# nguon.net
KiCad netlist of a schematic drawn in Altium Designer
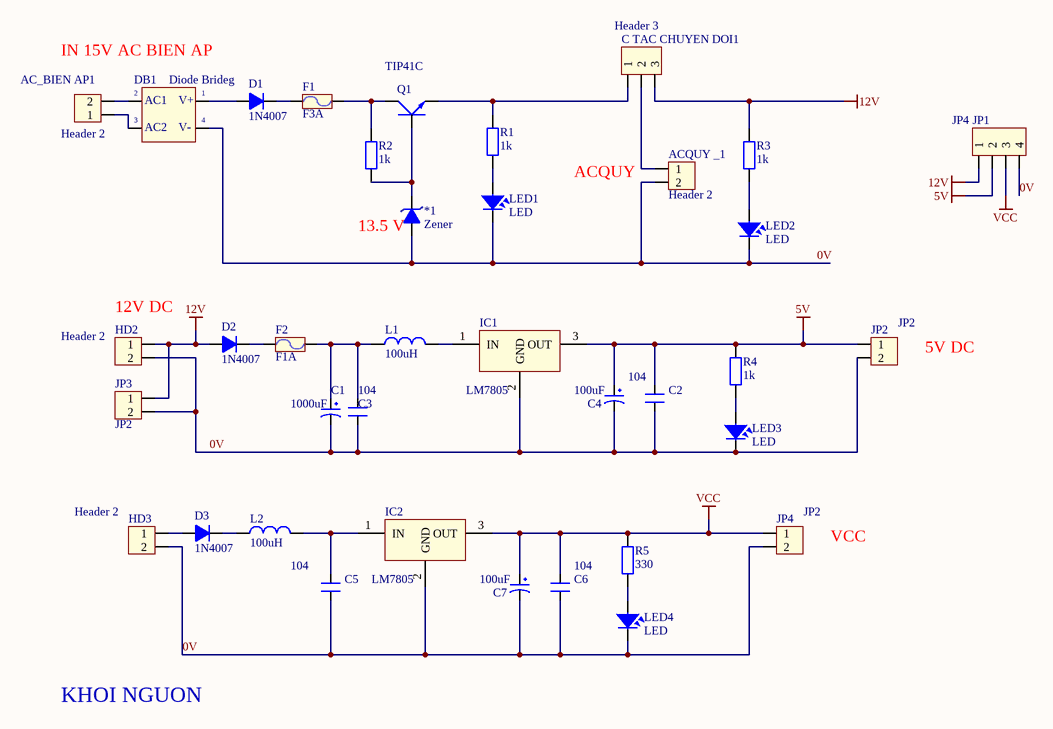
[diagram p0: nguon.SchDoc]

(export (version "E")
  (design (tool "Eeschema 10.0.6"))
  (components
    (comp (ref "*1") (value "Zener") (footprint "D1A") (libsource (lib "syhaunguyen") (part "Zener")))
    (comp (ref "ACQUY _1")
      (value "Header 2")
      (footprint "HED2")
      (description "Header 2 (Green)")
      (libsource (lib "") (part "Hed2_2"))
    )
    (comp (ref "AC_BIEN AP1")
      (value "Header 2")
      (footprint "HED2")
      (description "Header 2 (Green)")
      (libsource (lib "") (part "Hed2_1"))
    )
    (comp (ref "C TAC CHUYEN DOI1")
      (value "Header 3")
      (footprint "HED3")
      (description "Header 3 (Green)")
      (libsource (lib "syhaunguyen") (part "Hed3"))
    )
    (comp (ref "C1")
      (value "1000uF")
      (footprint "CP1.5/3.4")
      (description "Cap 1000uF/16V - 220uF/50V")
      (libsource (lib "syhaunguyen") (part "CP4"))
    )
    (comp (ref "C2")
      (value "104")
      (footprint "CN2")
      (description "Cap np Cremic Value  104pF => 105pF")
      (libsource (lib "syhaunguyen") (part "CN2"))
    )
    (comp (ref "C3")
      (value "104")
      (footprint "CN2")
      (description "Cap np Cremic Value  104pF => 105pF")
      (libsource (lib "syhaunguyen") (part "CN2"))
    )
    (comp (ref "C4")
      (value "100uF")
      (footprint "CP1/2.5")
      (description "C 47uF/50V , 220uF/16V")
      (libsource (lib "syhaunguyen") (part "CP2"))
    )
    (comp (ref "C5")
      (value "104")
      (footprint "CN2")
      (description "Cap np Cremic Value  104pF => 105pF")
      (libsource (lib "syhaunguyen") (part "CN2"))
    )
    (comp (ref "C6")
      (value "104")
      (footprint "CN2")
      (description "Cap np Cremic Value  104pF => 105pF")
      (libsource (lib "syhaunguyen") (part "CN2"))
    )
    (comp (ref "C7")
      (value "100uF")
      (footprint "CP1/2.5")
      (description "C 47uF/50V , 220uF/16V")
      (libsource (lib "syhaunguyen") (part "CP2"))
    )
    (comp (ref "D1")
      (value "1N4007")
      (footprint "D1A")
      (description "Diode 1A")
      (libsource (lib "syhaunguyen") (part "D1A"))
    )
    (comp (ref "D2")
      (value "1N4007")
      (footprint "D1A")
      (description "Diode 1A")
      (libsource (lib "syhaunguyen") (part "D1A"))
    )
    (comp (ref "D3")
      (value "1N4007")
      (footprint "D1A")
      (description "Diode 1A")
      (libsource (lib "syhaunguyen") (part "D1A"))
    )
    (comp (ref "DB1")
      (value "Diode Brideg")
      (footprint "CAU 1A")
      (description "Convert AC to DC voltage, 4 pin")
      (libsource (lib "syhaunguyen") (part "DB"))
    )
    (comp (ref "F1")
      (value "F3A")
      (footprint "Fuse")
      (description "Fuse")
      (fields (field (name "DESIGNED BY") "VanDungEvn"))
      (libsource (lib "syhaunguyen") (part "Fuse"))
    )
    (comp (ref "F2")
      (value "F1A")
      (footprint "Fuse")
      (description "Fuse")
      (fields (field (name "DESIGNED BY") "VanDungEvn"))
      (libsource (lib "syhaunguyen") (part "Fuse"))
    )
    (comp (ref "HD2")
      (value "Header 2")
      (footprint "HED2")
      (description "Header 2 (Green)")
      (libsource (lib "syhaunguyen") (part "Hed2"))
    )
    (comp (ref "HD3")
      (value "Header 2")
      (footprint "HED2")
      (description "Header 2 (Green)")
      (libsource (lib "syhaunguyen") (part "Hed2"))
    )
    (comp (ref "IC1")
      (value "LM7805")
      (footprint "QTO-220")
      (description "On ap +, from + 5 to + 24VDC")
      (libsource (lib "syhaunguyen") (part "LM78xx"))
    )
    (comp (ref "IC2")
      (value "LM7805")
      (footprint "QTO-220")
      (description "On ap +, from + 5 to + 24VDC")
      (libsource (lib "syhaunguyen") (part "LM78xx"))
    )
    (comp (ref "JP1")
      (value "JP4")
      (footprint "CON4")
      (description "Connector 4")
      (libsource (lib "syhaunguyen") (part "Con4"))
    )
    (comp (ref "JP2")
      (value "JP2")
      (footprint "CON2")
      (description "Connector 2")
      (libsource (lib "syhaunguyen") (part "Con2"))
    )
    (comp (ref "JP3")
      (value "JP2")
      (footprint "CON2")
      (description "Connector 2")
      (libsource (lib "") (part "Con2_1"))
    )
    (comp (ref "JP4")
      (value "JP2")
      (footprint "CON2")
      (description "Connector 2")
      (libsource (lib "syhaunguyen") (part "Con2"))
    )
    (comp (ref "L1")
      (value "100uH")
      (footprint "L/0.4")
      (description "Inductor")
      (libsource (lib "syhaunguyen") (part "L1"))
    )
    (comp (ref "L2")
      (value "100uH")
      (footprint "L/0.4")
      (description "Inductor")
      (libsource (lib "syhaunguyen") (part "L1"))
    )
    (comp (ref "LED1")
      (value "LED")
      (footprint "LED-3")
      (description "Led  Vuong")
      (libsource (lib "syhaunguyen") (part "LED"))
    )
    (comp (ref "LED2")
      (value "LED")
      (footprint "LED-3")
      (description "Led  Vuong")
      (libsource (lib "syhaunguyen") (part "LED"))
    )
    (comp (ref "LED3")
      (value "LED")
      (footprint "LED-3")
      (description "Led  Vuong")
      (libsource (lib "syhaunguyen") (part "LED"))
    )
    (comp (ref "LED4")
      (value "LED")
      (footprint "LED-3")
      (description "Led  Vuong")
      (libsource (lib "syhaunguyen") (part "LED"))
    )
    (comp (ref "Q1")
      (value "TIP41C")
      (footprint "QTO-220")
      (description "NPN 2W, BCE")
      (libsource (lib "syhaunguyen") (part "TIP41C"))
    )
    (comp (ref "R1")
      (value "1k")
      (footprint "R1/4W")
      (description "Resistor 1/4W")
      (libsource (lib "syhaunguyen") (part "R1/4W"))
    )
    (comp (ref "R2")
      (value "1k")
      (footprint "R1/4W")
      (description "Resistor 1/4W")
      (libsource (lib "syhaunguyen") (part "R1/4W"))
    )
    (comp (ref "R3")
      (value "1k")
      (footprint "R1/4W")
      (description "Resistor 1/4W")
      (libsource (lib "syhaunguyen") (part "R1/4W"))
    )
    (comp (ref "R4")
      (value "1k")
      (footprint "R1/4W")
      (description "Resistor 1/4W")
      (libsource (lib "syhaunguyen") (part "R1/4W"))
    )
    (comp (ref "R5")
      (value "330")
      (footprint "R1/4W")
      (description "Resistor 1/4W")
      (libsource (lib "syhaunguyen") (part "R1/4W"))
    )
  )
  (nets
    (net (code "1") (name "/0V") (class "Default")
      (node (ref "*1") (pin "1") (pinfunction "A_1") (pintype "passive"))
      (node (ref "ACQUY _1") (pin "2") (pinfunction "2_2") (pintype "passive"))
      (node (ref "C1") (pin "2") (pinfunction "2_2") (pintype "passive"))
      (node (ref "C2") (pin "1") (pinfunction "1_1") (pintype "passive"))
      (node (ref "C3") (pin "1") (pinfunction "1_1") (pintype "passive"))
      (node (ref "C4") (pin "2") (pinfunction "2_2") (pintype "passive"))
      (node (ref "C5") (pin "1") (pinfunction "1_1") (pintype "passive"))
      (node (ref "C6") (pin "1") (pinfunction "1_1") (pintype "passive"))
      (node (ref "C7") (pin "2") (pinfunction "2_2") (pintype "passive"))
      (node (ref "DB1") (pin "4") (pinfunction "-V_OUT_4") (pintype "passive"))
      (node (ref "HD2") (pin "2") (pinfunction "2_2") (pintype "passive"))
      (node (ref "HD3") (pin "2") (pinfunction "2_2") (pintype "passive"))
      (node (ref "IC1") (pin "2") (pinfunction "GND_2") (pintype "passive"))
      (node (ref "IC2") (pin "2") (pinfunction "GND_2") (pintype "passive"))
      (node (ref "JP1") (pin "4") (pinfunction "4_4") (pintype "passive"))
      (node (ref "JP2") (pin "2") (pinfunction "2_2") (pintype "passive"))
      (node (ref "JP3") (pin "2") (pinfunction "2_2") (pintype "passive"))
      (node (ref "JP4") (pin "2") (pinfunction "2_2") (pintype "passive"))
      (node (ref "LED1") (pin "2") (pinfunction "2_2") (pintype "passive"))
      (node (ref "LED2") (pin "2") (pinfunction "2_2") (pintype "passive"))
      (node (ref "LED3") (pin "2") (pinfunction "2_2") (pintype "passive"))
      (node (ref "LED4") (pin "2") (pinfunction "2_2") (pintype "passive"))
    )
    (net (code "4") (name "5V") (class "Default")
      (node (ref "C2") (pin "2") (pinfunction "2_2") (pintype "passive"))
      (node (ref "C4") (pin "1") (pinfunction "1_1") (pintype "passive"))
      (node (ref "IC1") (pin "3") (pinfunction "OUT_3") (pintype "passive"))
      (node (ref "JP1") (pin "2") (pinfunction "2_2") (pintype "passive"))
      (node (ref "JP2") (pin "1") (pinfunction "1_1") (pintype "passive"))
      (node (ref "R4") (pin "1") (pinfunction "1_1") (pintype "passive"))
    )
    (net (code "5") (name "12V") (class "Default")
      (node (ref "C TAC CHUYEN DOI1") (pin "3") (pinfunction "3_3") (pintype "passive"))
      (node (ref "D2") (pin "1") (pinfunction "A_1") (pintype "passive"))
      (node (ref "HD2") (pin "1") (pinfunction "1_1") (pintype "passive"))
      (node (ref "JP1") (pin "1") (pinfunction "1_1") (pintype "passive"))
      (node (ref "JP3") (pin "1") (pinfunction "1_1") (pintype "passive"))
      (node (ref "R3") (pin "2") (pinfunction "2_2") (pintype "passive"))
    )
    (net (code "6") (name "Net-(*1-K)") (class "Default")
      (node (ref "*1") (pin "2") (pinfunction "K_2") (pintype "passive"))
      (node (ref "Q1") (pin "1") (pinfunction "B_1") (pintype "passive"))
      (node (ref "R2") (pin "1") (pinfunction "1_1") (pintype "passive"))
    )
    (net (code "7") (name "Net-(ACQUY _1-Pad1)") (class "Default")
      (node (ref "ACQUY _1") (pin "1") (pinfunction "1_1") (pintype "passive"))
      (node (ref "C TAC CHUYEN DOI1") (pin "2") (pinfunction "2_2") (pintype "passive"))
    )
    (net (code "8") (name "Net-(C1-Pad1)") (class "Default")
      (node (ref "C1") (pin "1") (pinfunction "1_1") (pintype "passive"))
      (node (ref "C3") (pin "2") (pinfunction "2_2") (pintype "passive"))
      (node (ref "F2") (pin "2") (pinfunction "2_2") (pintype "passive"))
      (node (ref "L1") (pin "1") (pinfunction "1_1") (pintype "passive"))
    )
    (net (code "9") (name "Net-(D1-A)") (class "Default")
      (node (ref "D1") (pin "1") (pinfunction "A_1") (pintype "passive"))
      (node (ref "DB1") (pin "1") (pinfunction "+V_OUT_1") (pintype "passive"))
    )
    (net (code "10") (name "Net-(D1-K)") (class "Default")
      (node (ref "D1") (pin "2") (pinfunction "K_2") (pintype "passive"))
      (node (ref "F1") (pin "1") (pinfunction "1_1") (pintype "passive"))
    )
    (net (code "11") (name "Net-(D2-K)") (class "Default")
      (node (ref "D2") (pin "2") (pinfunction "K_2") (pintype "passive"))
      (node (ref "F2") (pin "1") (pinfunction "1_1") (pintype "passive"))
    )
    (net (code "12") (name "Net-(D3-A)") (class "Default")
      (node (ref "D3") (pin "1") (pinfunction "A_1") (pintype "passive"))
      (node (ref "HD3") (pin "1") (pinfunction "1_1") (pintype "passive"))
    )
    (net (code "13") (name "Net-(D3-K)") (class "Default")
      (node (ref "D3") (pin "2") (pinfunction "K_2") (pintype "passive"))
      (node (ref "L2") (pin "1") (pinfunction "1_1") (pintype "passive"))
    )
    (net (code "14") (name "Net-(DB1-AC1)") (class "Default")
      (node (ref "AC_BIEN AP1") (pin "2") (pinfunction "2_2") (pintype "passive"))
      (node (ref "DB1") (pin "2") (pinfunction "AC1_2") (pintype "passive"))
    )
    (net (code "15") (name "Net-(DB1-AC2)") (class "Default")
      (node (ref "AC_BIEN AP1") (pin "1") (pinfunction "1_1") (pintype "passive"))
      (node (ref "DB1") (pin "3") (pinfunction "AC2_3") (pintype "passive"))
    )
    (net (code "16") (name "Net-(IC1-IN)") (class "Default")
      (node (ref "IC1") (pin "1") (pinfunction "IN_1") (pintype "passive"))
      (node (ref "L1") (pin "2") (pinfunction "2_2") (pintype "passive"))
    )
    (net (code "17") (name "Net-(IC2-IN)") (class "Default")
      (node (ref "C5") (pin "2") (pinfunction "2_2") (pintype "passive"))
      (node (ref "IC2") (pin "1") (pinfunction "IN_1") (pintype "passive"))
      (node (ref "L2") (pin "2") (pinfunction "2_2") (pintype "passive"))
    )
    (net (code "18") (name "Net-(LED1-Pad1)") (class "Default")
      (node (ref "LED1") (pin "1") (pinfunction "1_1") (pintype "passive"))
      (node (ref "R1") (pin "1") (pinfunction "1_1") (pintype "passive"))
    )
    (net (code "19") (name "Net-(LED2-Pad1)") (class "Default")
      (node (ref "LED2") (pin "1") (pinfunction "1_1") (pintype "passive"))
      (node (ref "R3") (pin "1") (pinfunction "1_1") (pintype "passive"))
    )
    (net (code "20") (name "Net-(LED3-Pad1)") (class "Default")
      (node (ref "LED3") (pin "1") (pinfunction "1_1") (pintype "passive"))
      (node (ref "R4") (pin "2") (pinfunction "2_2") (pintype "passive"))
    )
    (net (code "21") (name "Net-(LED4-Pad1)") (class "Default")
      (node (ref "LED4") (pin "1") (pinfunction "1_1") (pintype "passive"))
      (node (ref "R5") (pin "2") (pinfunction "2_2") (pintype "passive"))
    )
    (net (code "22") (name "Net-(Q1-C)") (class "Default")
      (node (ref "F1") (pin "2") (pinfunction "2_2") (pintype "passive"))
      (node (ref "Q1") (pin "2") (pinfunction "C_2") (pintype "passive"))
      (node (ref "R2") (pin "2") (pinfunction "2_2") (pintype "passive"))
    )
    (net (code "23") (name "Net-(Q1-E)") (class "Default")
      (node (ref "C TAC CHUYEN DOI1") (pin "1") (pinfunction "1_1") (pintype "passive"))
      (node (ref "Q1") (pin "3") (pinfunction "E_3") (pintype "passive"))
      (node (ref "R1") (pin "2") (pinfunction "2_2") (pintype "passive"))
    )
    (net (code "24") (name "VCC") (class "Default")
      (node (ref "C6") (pin "2") (pinfunction "2_2") (pintype "passive"))
      (node (ref "C7") (pin "1") (pinfunction "1_1") (pintype "passive"))
      (node (ref "IC2") (pin "3") (pinfunction "OUT_3") (pintype "passive"))
      (node (ref "JP1") (pin "3") (pinfunction "3_3") (pintype "passive"))
      (node (ref "JP4") (pin "1") (pinfunction "1_1") (pintype "passive"))
      (node (ref "R5") (pin "1") (pinfunction "1_1") (pintype "passive"))
    )
  )
)
